# TESTPOINTS.net
KiCad netlist of a schematic drawn in Altium Designer
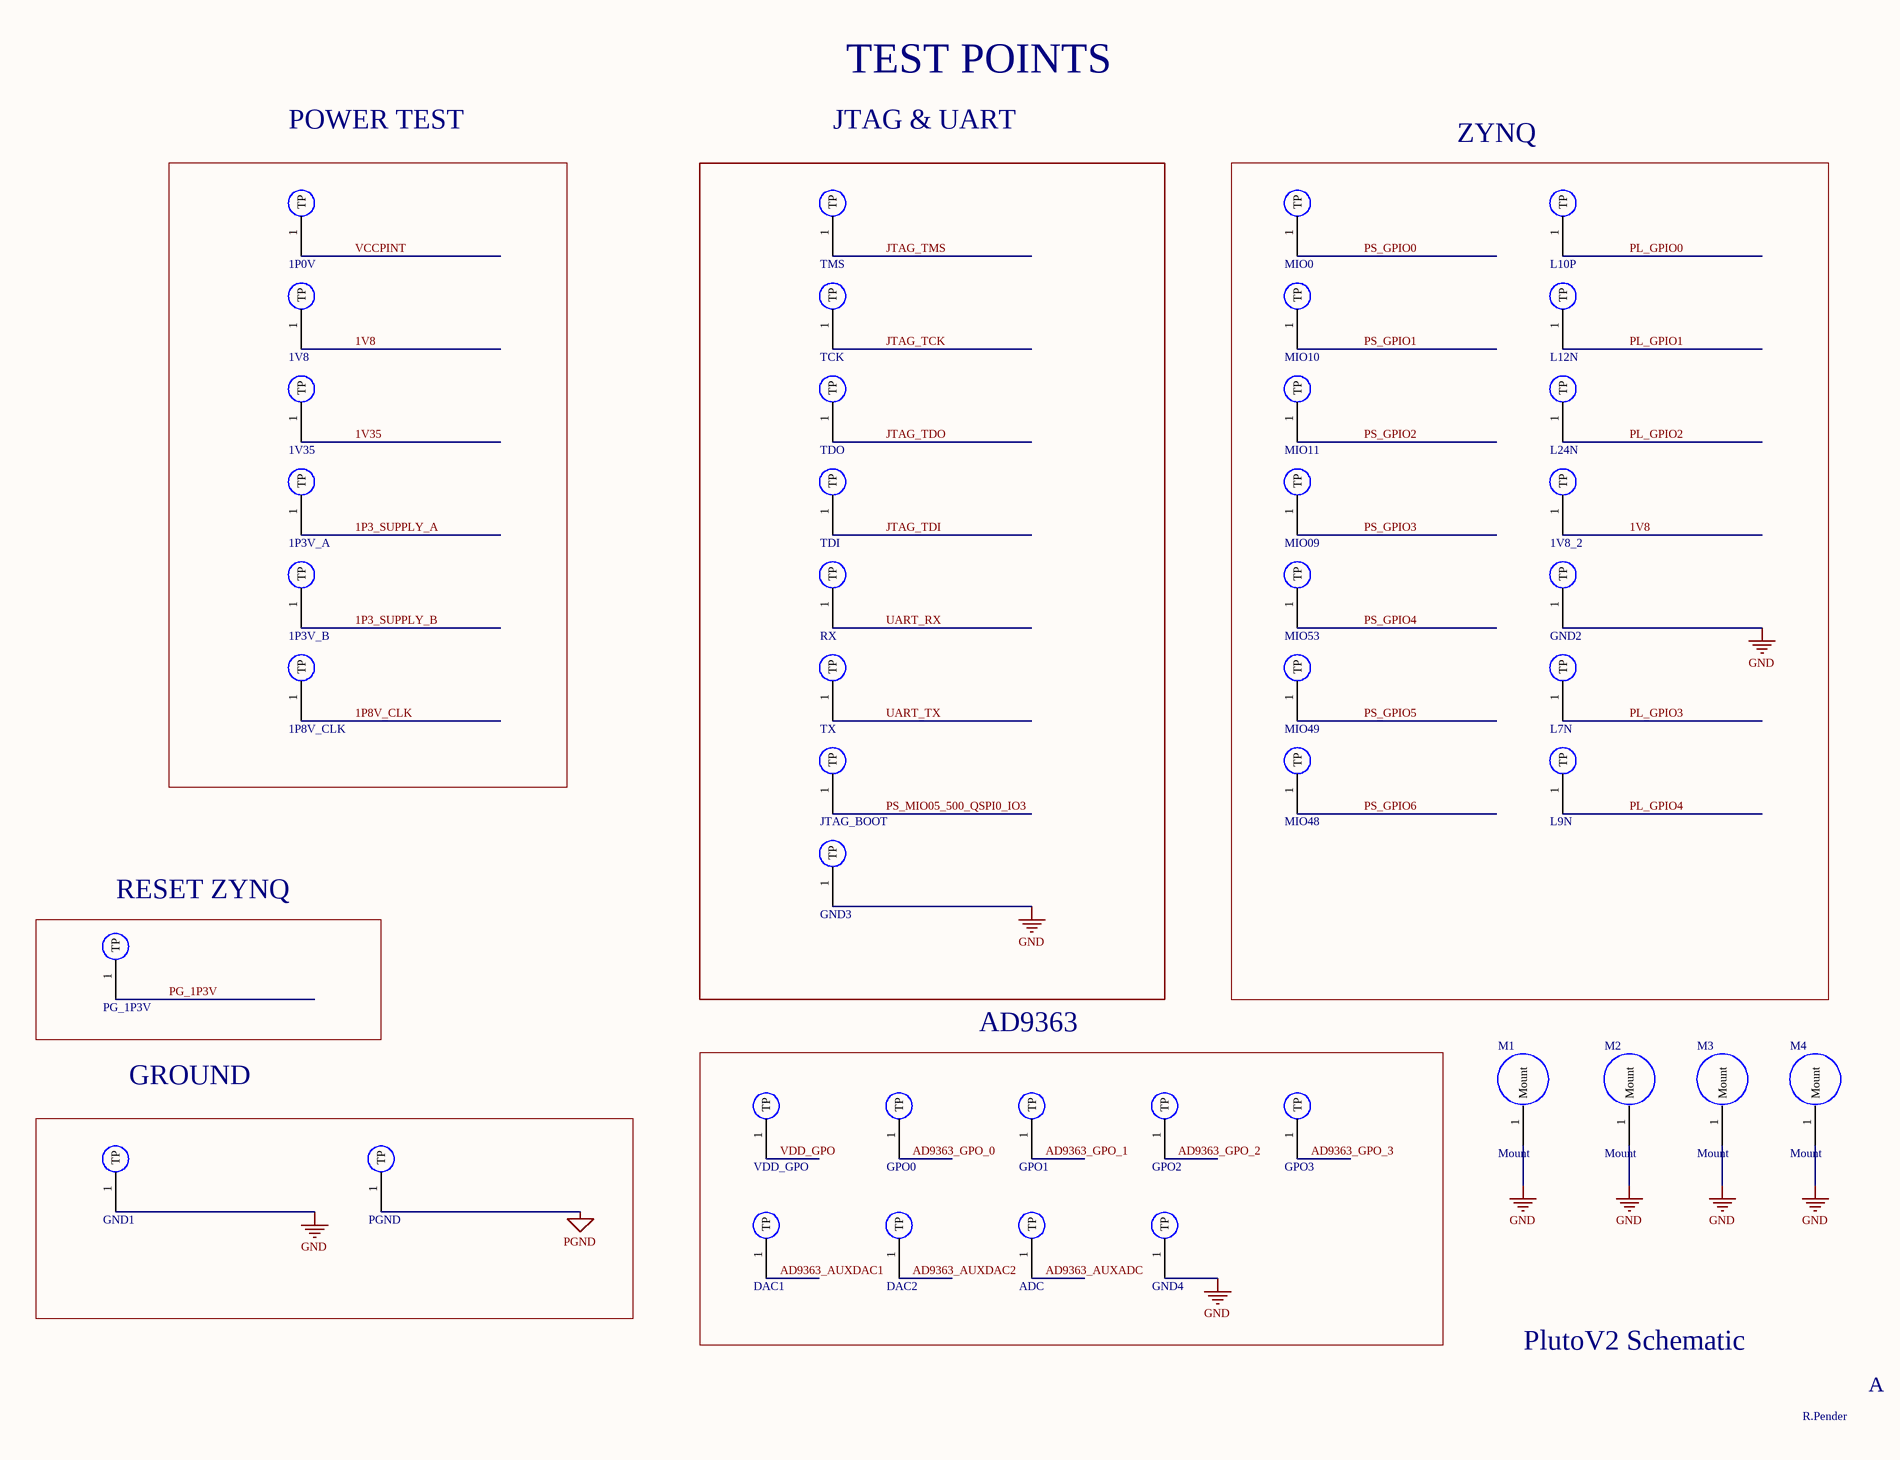
[diagram p0: TESTPOINTS.SchDoc, left]
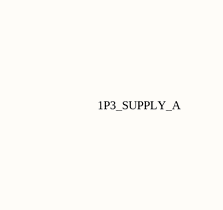
[diagram p1: TESTPOINTS.SchDoc, right]

(export (version "E")
  (design (tool "Eeschema 10.0.6"))
  (components
    (comp (ref "1P0V")
      (value "TEST POINT")
      (footprint "TESTPOINT1")
      (libsource (lib "RINALDOSCHEMS") (part "TESTPT"))
    )
    (comp (ref "1P3V_A")
      (value "TEST POINT")
      (footprint "TESTPOINT1")
      (libsource (lib "RINALDOSCHEMS") (part "TESTPT"))
    )
    (comp (ref "1P3V_B")
      (value "TEST POINT")
      (footprint "TESTPOINT1")
      (libsource (lib "RINALDOSCHEMS") (part "TESTPT"))
    )
    (comp (ref "1P8V_CLK")
      (value "TEST POINT")
      (footprint "TESTPOINT1")
      (libsource (lib "RINALDOSCHEMS") (part "TESTPT"))
    )
    (comp (ref "1V8")
      (value "TEST POINT")
      (footprint "TESTPOINT1")
      (libsource (lib "RINALDOSCHEMS") (part "TESTPT"))
    )
    (comp (ref "1V8_2")
      (value "TEST POINT")
      (footprint "TESTPOINT1")
      (libsource (lib "RINALDOSCHEMS") (part "TESTPT"))
    )
    (comp (ref "1V35")
      (value "TEST POINT")
      (footprint "TESTPOINT1")
      (libsource (lib "RINALDOSCHEMS") (part "TESTPT"))
    )
    (comp (ref "ADC")
      (value "TEST POINT")
      (footprint "TESTPOINT1")
      (libsource (lib "RINALDOSCHEMS") (part "TESTPT"))
    )
    (comp (ref "DAC1")
      (value "TEST POINT")
      (footprint "TESTPOINT1")
      (libsource (lib "RINALDOSCHEMS") (part "TESTPT"))
    )
    (comp (ref "DAC2")
      (value "TEST POINT")
      (footprint "TESTPOINT1")
      (libsource (lib "RINALDOSCHEMS") (part "TESTPT"))
    )
    (comp (ref "GND1")
      (value "TEST POINT")
      (footprint "TESTPOINT1")
      (libsource (lib "RINALDOSCHEMS") (part "TESTPT"))
    )
    (comp (ref "GND2")
      (value "TEST POINT")
      (footprint "TESTPOINT1")
      (libsource (lib "RINALDOSCHEMS") (part "TESTPT"))
    )
    (comp (ref "GND3")
      (value "TEST POINT")
      (footprint "TESTPOINT1")
      (libsource (lib "RINALDOSCHEMS") (part "TESTPT"))
    )
    (comp (ref "GND4")
      (value "TEST POINT")
      (footprint "TESTPOINT1")
      (libsource (lib "RINALDOSCHEMS") (part "TESTPT"))
    )
    (comp (ref "GPO0")
      (value "TEST POINT")
      (footprint "TESTPOINT1")
      (libsource (lib "RINALDOSCHEMS") (part "TESTPT"))
    )
    (comp (ref "GPO1")
      (value "TEST POINT")
      (footprint "TESTPOINT1")
      (libsource (lib "RINALDOSCHEMS") (part "TESTPT"))
    )
    (comp (ref "GPO2")
      (value "TEST POINT")
      (footprint "TESTPOINT1")
      (libsource (lib "RINALDOSCHEMS") (part "TESTPT"))
    )
    (comp (ref "GPO3")
      (value "TEST POINT")
      (footprint "TESTPOINT1")
      (libsource (lib "RINALDOSCHEMS") (part "TESTPT"))
    )
    (comp (ref "JTAG_BOOT")
      (value "TEST POINT")
      (footprint "TESTPOINT1")
      (libsource (lib "RINALDOSCHEMS") (part "TESTPT"))
    )
    (comp (ref "L7N")
      (value "TEST POINT")
      (footprint "TESTPOINT1")
      (libsource (lib "RINALDOSCHEMS") (part "TESTPT"))
    )
    (comp (ref "L9N")
      (value "TEST POINT")
      (footprint "TESTPOINT1")
      (libsource (lib "RINALDOSCHEMS") (part "TESTPT"))
    )
    (comp (ref "L10P")
      (value "TEST POINT")
      (footprint "TESTPOINT1")
      (libsource (lib "RINALDOSCHEMS") (part "TESTPT"))
    )
    (comp (ref "L12N")
      (value "TEST POINT")
      (footprint "TESTPOINT1")
      (libsource (lib "RINALDOSCHEMS") (part "TESTPT"))
    )
    (comp (ref "L24N")
      (value "TEST POINT")
      (footprint "TESTPOINT1")
      (libsource (lib "RINALDOSCHEMS") (part "TESTPT"))
    )
    (comp (ref "M1") (value "Mount") (footprint "Mount") (libsource (lib "RINALDOSCHEMS") (part "Mount")))
    (comp (ref "M2") (value "Mount") (footprint "Mount") (libsource (lib "RINALDOSCHEMS") (part "Mount")))
    (comp (ref "M3") (value "Mount") (footprint "Mount") (libsource (lib "RINALDOSCHEMS") (part "Mount")))
    (comp (ref "M4") (value "Mount") (footprint "Mount") (libsource (lib "RINALDOSCHEMS") (part "Mount")))
    (comp (ref "MIO0")
      (value "TEST POINT")
      (footprint "TESTPOINT1")
      (libsource (lib "RINALDOSCHEMS") (part "TESTPT"))
    )
    (comp (ref "MIO09")
      (value "TEST POINT")
      (footprint "TESTPOINT1")
      (libsource (lib "RINALDOSCHEMS") (part "TESTPT"))
    )
    (comp (ref "MIO10")
      (value "TEST POINT")
      (footprint "TESTPOINT1")
      (libsource (lib "RINALDOSCHEMS") (part "TESTPT"))
    )
    (comp (ref "MIO11")
      (value "TEST POINT")
      (footprint "TESTPOINT1")
      (libsource (lib "RINALDOSCHEMS") (part "TESTPT"))
    )
    (comp (ref "MIO48")
      (value "TEST POINT")
      (footprint "TESTPOINT1")
      (libsource (lib "RINALDOSCHEMS") (part "TESTPT"))
    )
    (comp (ref "MIO49")
      (value "TEST POINT")
      (footprint "TESTPOINT1")
      (libsource (lib "RINALDOSCHEMS") (part "TESTPT"))
    )
    (comp (ref "MIO53")
      (value "TEST POINT")
      (footprint "TESTPOINT1")
      (libsource (lib "RINALDOSCHEMS") (part "TESTPT"))
    )
    (comp (ref "PGND")
      (value "TEST POINT")
      (footprint "TESTPOINT1")
      (libsource (lib "RINALDOSCHEMS") (part "TESTPT"))
    )
    (comp (ref "PG_1P3V")
      (value "TEST POINT")
      (footprint "TESTPOINT1")
      (libsource (lib "RINALDOSCHEMS") (part "TESTPT"))
    )
    (comp (ref "RX")
      (value "TEST POINT")
      (footprint "TESTPOINT1")
      (libsource (lib "RINALDOSCHEMS") (part "TESTPT"))
    )
    (comp (ref "TCK")
      (value "TEST POINT")
      (footprint "TESTPOINT1")
      (libsource (lib "RINALDOSCHEMS") (part "TESTPT"))
    )
    (comp (ref "TDI")
      (value "TEST POINT")
      (footprint "TESTPOINT1")
      (libsource (lib "RINALDOSCHEMS") (part "TESTPT"))
    )
    (comp (ref "TDO")
      (value "TEST POINT")
      (footprint "TESTPOINT1")
      (libsource (lib "RINALDOSCHEMS") (part "TESTPT"))
    )
    (comp (ref "TMS")
      (value "TEST POINT")
      (footprint "TESTPOINT1")
      (libsource (lib "RINALDOSCHEMS") (part "TESTPT"))
    )
    (comp (ref "TX")
      (value "TEST POINT")
      (footprint "TESTPOINT1")
      (libsource (lib "RINALDOSCHEMS") (part "TESTPT"))
    )
    (comp (ref "VDD_GPO")
      (value "TEST POINT")
      (footprint "TESTPOINT1")
      (libsource (lib "RINALDOSCHEMS") (part "TESTPT"))
    )
  )
  (nets
    (net (code "1") (name "/1P3_SUPPLY_A") (class "Default")
      (node (ref "1P3V_A") (pin "1") (pinfunction "TP_1") (pintype "passive"))
    )
    (net (code "2") (name "/1P3_SUPPLY_B") (class "Default")
      (node (ref "1P3V_B") (pin "1") (pinfunction "TP_1") (pintype "passive"))
    )
    (net (code "3") (name "/1P8V_CLK") (class "Default")
      (node (ref "1P8V_CLK") (pin "1") (pinfunction "TP_1") (pintype "passive"))
    )
    (net (code "4") (name "/1V8") (class "Default")
      (node (ref "1V8") (pin "1") (pinfunction "TP_1") (pintype "passive"))
      (node (ref "1V8_2") (pin "1") (pinfunction "TP_1") (pintype "passive"))
    )
    (net (code "5") (name "/1V35") (class "Default")
      (node (ref "1V35") (pin "1") (pinfunction "TP_1") (pintype "passive"))
    )
    (net (code "6") (name "/AD9363_AUXADC") (class "Default")
      (node (ref "ADC") (pin "1") (pinfunction "TP_1") (pintype "passive"))
    )
    (net (code "7") (name "/AD9363_AUXDAC1") (class "Default")
      (node (ref "DAC1") (pin "1") (pinfunction "TP_1") (pintype "passive"))
    )
    (net (code "8") (name "/AD9363_AUXDAC2") (class "Default")
      (node (ref "DAC2") (pin "1") (pinfunction "TP_1") (pintype "passive"))
    )
    (net (code "9") (name "/AD9363_GPO_0") (class "Default")
      (node (ref "GPO0") (pin "1") (pinfunction "TP_1") (pintype "passive"))
    )
    (net (code "10") (name "/AD9363_GPO_1") (class "Default")
      (node (ref "GPO1") (pin "1") (pinfunction "TP_1") (pintype "passive"))
    )
    (net (code "11") (name "/AD9363_GPO_2") (class "Default")
      (node (ref "GPO2") (pin "1") (pinfunction "TP_1") (pintype "passive"))
    )
    (net (code "12") (name "/AD9363_GPO_3") (class "Default")
      (node (ref "GPO3") (pin "1") (pinfunction "TP_1") (pintype "passive"))
    )
    (net (code "13") (name "/JTAG_TCK") (class "Default")
      (node (ref "TCK") (pin "1") (pinfunction "TP_1") (pintype "passive"))
    )
    (net (code "14") (name "/JTAG_TDI") (class "Default")
      (node (ref "TDI") (pin "1") (pinfunction "TP_1") (pintype "passive"))
    )
    (net (code "15") (name "/JTAG_TDO") (class "Default")
      (node (ref "TDO") (pin "1") (pinfunction "TP_1") (pintype "passive"))
    )
    (net (code "16") (name "/JTAG_TMS") (class "Default")
      (node (ref "TMS") (pin "1") (pinfunction "TP_1") (pintype "passive"))
    )
    (net (code "17") (name "/PG_1P3V") (class "Default")
      (node (ref "PG_1P3V") (pin "1") (pinfunction "TP_1") (pintype "passive"))
    )
    (net (code "18") (name "/PL_GPIO0") (class "Default")
      (node (ref "L10P") (pin "1") (pinfunction "TP_1") (pintype "passive"))
    )
    (net (code "19") (name "/PL_GPIO1") (class "Default")
      (node (ref "L12N") (pin "1") (pinfunction "TP_1") (pintype "passive"))
    )
    (net (code "20") (name "/PL_GPIO2") (class "Default")
      (node (ref "L24N") (pin "1") (pinfunction "TP_1") (pintype "passive"))
    )
    (net (code "21") (name "/PL_GPIO3") (class "Default")
      (node (ref "L7N") (pin "1") (pinfunction "TP_1") (pintype "passive"))
    )
    (net (code "22") (name "/PL_GPIO4") (class "Default")
      (node (ref "L9N") (pin "1") (pinfunction "TP_1") (pintype "passive"))
    )
    (net (code "23") (name "/PS_GPIO0") (class "Default")
      (node (ref "MIO0") (pin "1") (pinfunction "TP_1") (pintype "passive"))
    )
    (net (code "24") (name "/PS_GPIO1") (class "Default")
      (node (ref "MIO10") (pin "1") (pinfunction "TP_1") (pintype "passive"))
    )
    (net (code "25") (name "/PS_GPIO2") (class "Default")
      (node (ref "MIO11") (pin "1") (pinfunction "TP_1") (pintype "passive"))
    )
    (net (code "26") (name "/PS_GPIO3") (class "Default")
      (node (ref "MIO09") (pin "1") (pinfunction "TP_1") (pintype "passive"))
    )
    (net (code "27") (name "/PS_GPIO4") (class "Default")
      (node (ref "MIO53") (pin "1") (pinfunction "TP_1") (pintype "passive"))
    )
    (net (code "28") (name "/PS_GPIO5") (class "Default")
      (node (ref "MIO49") (pin "1") (pinfunction "TP_1") (pintype "passive"))
    )
    (net (code "29") (name "/PS_GPIO6") (class "Default")
      (node (ref "MIO48") (pin "1") (pinfunction "TP_1") (pintype "passive"))
    )
    (net (code "30") (name "/PS_MIO05_500_QSPI0_IO3") (class "Default")
      (node (ref "JTAG_BOOT") (pin "1") (pinfunction "TP_1") (pintype "passive"))
    )
    (net (code "31") (name "/UART_RX") (class "Default")
      (node (ref "RX") (pin "1") (pinfunction "TP_1") (pintype "passive"))
    )
    (net (code "32") (name "/UART_TX") (class "Default")
      (node (ref "TX") (pin "1") (pinfunction "TP_1") (pintype "passive"))
    )
    (net (code "33") (name "/VCCPINT") (class "Default")
      (node (ref "1P0V") (pin "1") (pinfunction "TP_1") (pintype "passive"))
    )
    (net (code "34") (name "/VDD_GPO") (class "Default")
      (node (ref "VDD_GPO") (pin "1") (pinfunction "TP_1") (pintype "passive"))
    )
    (net (code "35") (name "GND") (class "Default")
      (node (ref "GND1") (pin "1") (pinfunction "TP_1") (pintype "passive"))
      (node (ref "GND2") (pin "1") (pinfunction "TP_1") (pintype "passive"))
      (node (ref "GND3") (pin "1") (pinfunction "TP_1") (pintype "passive"))
      (node (ref "GND4") (pin "1") (pinfunction "TP_1") (pintype "passive"))
      (node (ref "M1") (pin "1") (pinfunction "Mount_1") (pintype "passive"))
      (node (ref "M2") (pin "1") (pinfunction "Mount_1") (pintype "passive"))
      (node (ref "M3") (pin "1") (pinfunction "Mount_1") (pintype "passive"))
      (node (ref "M4") (pin "1") (pinfunction "Mount_1") (pintype "passive"))
    )
    (net (code "36") (name "PGND") (class "Default")
      (node (ref "PGND") (pin "1") (pinfunction "TP_1") (pintype "passive"))
    )
  )
)
